# ApplicationShield.net
KiCad netlist of a schematic drawn in EAGLE
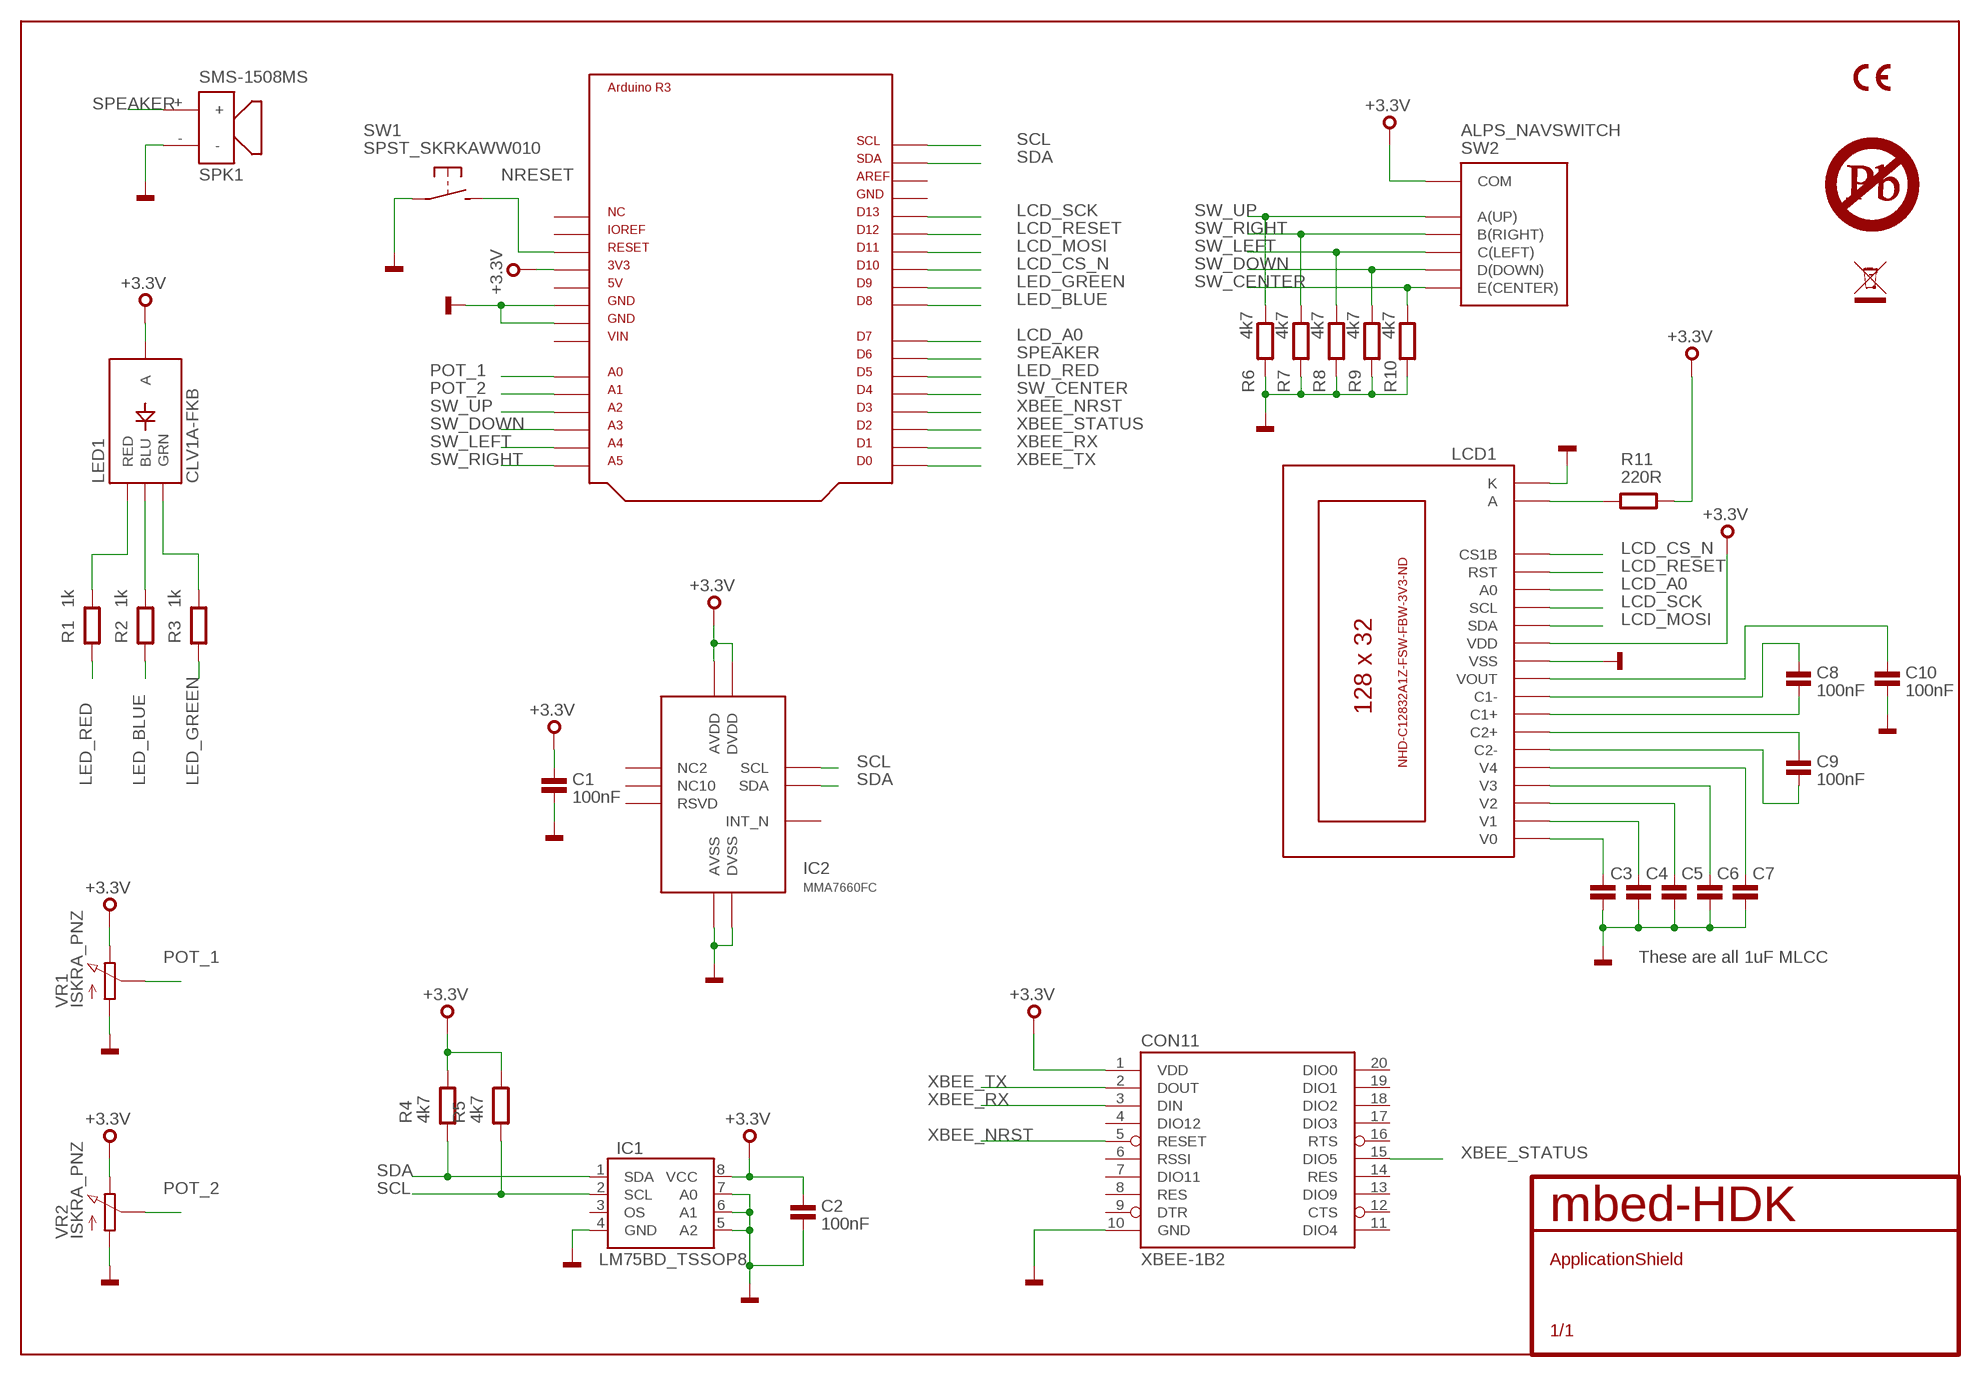
[diagram p0: schematic, sheet 1]

(export (version "E")
  (design (tool "Eeschema 10.0.6"))
  (components
    (comp (ref "BRD1")
      (value "ARDUINO_R3_APPS")
      (footprint "eagle-import:ARDUINO_R3_APPS_SHEILD")
      (libsource (lib "eagle-import") (part "ARDUINO_R3_APPS"))
    )
    (comp (ref "C1")
      (value "100nF")
      (footprint "eagle-import:0402")
      (libsource (lib "eagle-import") (part "C0402"))
    )
    (comp (ref "C2")
      (value "100nF")
      (footprint "eagle-import:0402")
      (libsource (lib "eagle-import") (part "C0402"))
    )
    (comp (ref "C3")
      (value "100nF")
      (footprint "eagle-import:0402")
      (libsource (lib "eagle-import") (part "C0402"))
    )
    (comp (ref "C4")
      (value "100nF")
      (footprint "eagle-import:0402")
      (libsource (lib "eagle-import") (part "C0402"))
    )
    (comp (ref "C5")
      (value "100nF")
      (footprint "eagle-import:0402")
      (libsource (lib "eagle-import") (part "C0402"))
    )
    (comp (ref "C6")
      (value "100nF")
      (footprint "eagle-import:0402")
      (libsource (lib "eagle-import") (part "C0402"))
    )
    (comp (ref "C7")
      (value "100nF")
      (footprint "eagle-import:0402")
      (libsource (lib "eagle-import") (part "C0402"))
    )
    (comp (ref "C8")
      (value "100nF")
      (footprint "eagle-import:0402")
      (libsource (lib "eagle-import") (part "C0402"))
    )
    (comp (ref "C9")
      (value "100nF")
      (footprint "eagle-import:0402")
      (libsource (lib "eagle-import") (part "C0402"))
    )
    (comp (ref "C10")
      (value "100nF")
      (footprint "eagle-import:0402")
      (libsource (lib "eagle-import") (part "C0402"))
    )
    (comp (ref "CON11")
      (value "XBEE-1B2")
      (footprint "eagle-import:XBEE-SILK")
      (libsource (lib "eagle-import") (part "XBEE-1B2"))
    )
    (comp (ref "IC1")
      (value "LM75BD_TSSOP8")
      (footprint "eagle-import:TSSOP8")
      (libsource (lib "eagle-import") (part "LM75BD_TSSOP8"))
    )
    (comp (ref "IC2")
      (value "MMA7660FC")
      (footprint "eagle-import:DFN10-3X3MM")
      (libsource (lib "eagle-import") (part "MMA7660FC"))
    )
    (comp (ref "LCD1")
      (value "C12832A1Z")
      (footprint "eagle-import:C12832A1Z")
      (libsource (lib "eagle-import") (part "C12832A1Z"))
    )
    (comp (ref "LED1")
      (value "CLV1A-FKB")
      (footprint "eagle-import:PLCC-4")
      (libsource (lib "eagle-import") (part "CLV1A-FKB"))
    )
    (comp (ref "R1")
      (value "1k")
      (footprint "eagle-import:0402")
      (libsource (lib "eagle-import") (part "R0402"))
    )
    (comp (ref "R2")
      (value "1k")
      (footprint "eagle-import:0402")
      (libsource (lib "eagle-import") (part "R0402"))
    )
    (comp (ref "R3")
      (value "1k")
      (footprint "eagle-import:0402")
      (libsource (lib "eagle-import") (part "R0402"))
    )
    (comp (ref "R4")
      (value "4k7")
      (footprint "eagle-import:0402")
      (libsource (lib "eagle-import") (part "R0402"))
    )
    (comp (ref "R5")
      (value "4k7")
      (footprint "eagle-import:0402")
      (libsource (lib "eagle-import") (part "R0402"))
    )
    (comp (ref "R6")
      (value "4k7")
      (footprint "eagle-import:0402")
      (libsource (lib "eagle-import") (part "R0402"))
    )
    (comp (ref "R7")
      (value "4k7")
      (footprint "eagle-import:0402")
      (libsource (lib "eagle-import") (part "R0402"))
    )
    (comp (ref "R8")
      (value "4k7")
      (footprint "eagle-import:0402")
      (libsource (lib "eagle-import") (part "R0402"))
    )
    (comp (ref "R9")
      (value "4k7")
      (footprint "eagle-import:0402")
      (libsource (lib "eagle-import") (part "R0402"))
    )
    (comp (ref "R10")
      (value "4k7")
      (footprint "eagle-import:0402")
      (libsource (lib "eagle-import") (part "R0402"))
    )
    (comp (ref "R11")
      (value "220R")
      (footprint "eagle-import:0402")
      (libsource (lib "eagle-import") (part "R0402"))
    )
    (comp (ref "SPK1")
      (value "SMS-1508MS")
      (footprint "eagle-import:SMS-1508MS-R")
      (libsource (lib "eagle-import") (part "SMS-1508MS"))
    )
    (comp (ref "SS1")
      (value "PB-MARK")
      (footprint "eagle-import:PB-MARK-0.2")
      (libsource (lib "eagle-import") (part "PB-MARK"))
    )
    (comp (ref "SS2")
      (value "CE-MARK")
      (footprint "eagle-import:CE-MARK-0.2")
      (libsource (lib "eagle-import") (part "CE-MARK"))
    )
    (comp (ref "SS3")
      (value "WEEE-MARK")
      (footprint "eagle-import:WEEE-MARK-0.2")
      (libsource (lib "eagle-import") (part "WEEE-MARK"))
    )
    (comp (ref "SW1")
      (value "SPST_SKRKAWW010")
      (footprint "eagle-import:SKRKAEE010")
      (libsource (lib "eagle-import") (part "SPST_SKRKAWW010"))
    )
    (comp (ref "SW2")
      (value "ALPS_NAVSWITCH")
      (footprint "eagle-import:SKRHA_SERIES")
      (libsource (lib "eagle-import") (part "ALPS_NAVSWITCH"))
    )
    (comp (ref "VR1")
      (value "ISKRA_PNZ")
      (footprint "eagle-import:CA14V")
      (libsource (lib "eagle-import") (part "ISKRA_PNZ"))
    )
    (comp (ref "VR2")
      (value "ISKRA_PNZ")
      (footprint "eagle-import:CA14V")
      (libsource (lib "eagle-import") (part "ISKRA_PNZ"))
    )
  )
  (nets
    (net (code "1") (name "+3.3V") (class "Default")
      (node (ref "BRD1") (pin "P$4") (pinfunction "P$4_P$4") (pintype "bidirectional"))
      (node (ref "C1") (pin "1") (pinfunction "P$1_1") (pintype "passive"))
      (node (ref "C2") (pin "1") (pinfunction "P$1_1") (pintype "passive"))
      (node (ref "CON11") (pin "1") (pinfunction "VDD_1") (pintype "passive"))
      (node (ref "IC1") (pin "8") (pinfunction "VCC_8") (pintype "bidirectional"))
      (node (ref "IC2") (pin "P$3") (pinfunction "AVDD_P$3") (pintype "bidirectional"))
      (node (ref "IC2") (pin "P$9") (pinfunction "DVDD_P$9") (pintype "bidirectional"))
      (node (ref "LCD1") (pin "P$12") (pinfunction "VDD_P$12") (pintype "bidirectional"))
      (node (ref "LED1") (pin "2") (pinfunction "A_2") (pintype "bidirectional"))
      (node (ref "R11") (pin "1") (pinfunction "P$1_1") (pintype "passive"))
      (node (ref "R4") (pin "2") (pinfunction "P$2_2") (pintype "passive"))
      (node (ref "R5") (pin "2") (pinfunction "P$2_2") (pintype "passive"))
      (node (ref "SW2") (pin "P$5") (pinfunction "COM_P$5") (pintype "bidirectional"))
      (node (ref "VR1") (pin "P$3") (pinfunction "E_P$3") (pintype "passive"))
      (node (ref "VR2") (pin "P$3") (pinfunction "E_P$3") (pintype "passive"))
    )
    (net (code "2") (name "/LCD_A0") (class "Default")
      (node (ref "BRD1") (pin "P$22") (pinfunction "P$22_P$22") (pintype "bidirectional"))
      (node (ref "LCD1") (pin "P$15") (pinfunction "A0_P$15") (pintype "bidirectional"))
    )
    (net (code "3") (name "/LCD_CS_N") (class "Default")
      (node (ref "BRD1") (pin "P$25") (pinfunction "P$25_P$25") (pintype "bidirectional"))
      (node (ref "LCD1") (pin "P$17") (pinfunction "CS1B_P$17") (pintype "bidirectional"))
    )
    (net (code "4") (name "/LCD_MOSI") (class "Default")
      (node (ref "BRD1") (pin "P$26") (pinfunction "P$26_P$26") (pintype "bidirectional"))
      (node (ref "LCD1") (pin "P$13") (pinfunction "SDA_P$13") (pintype "bidirectional"))
    )
    (net (code "5") (name "/LCD_RESET") (class "Default")
      (node (ref "BRD1") (pin "P$27") (pinfunction "P$27_P$27") (pintype "bidirectional"))
      (node (ref "LCD1") (pin "P$16") (pinfunction "RST_P$16") (pintype "bidirectional"))
    )
    (net (code "6") (name "/LCD_SCK") (class "Default")
      (node (ref "BRD1") (pin "P$28") (pinfunction "P$28_P$28") (pintype "bidirectional"))
      (node (ref "LCD1") (pin "P$14") (pinfunction "SCL_P$14") (pintype "bidirectional"))
    )
    (net (code "7") (name "/LED_BLUE") (class "Default")
      (node (ref "BRD1") (pin "P$23") (pinfunction "P$23_P$23") (pintype "bidirectional"))
      (node (ref "R2") (pin "1") (pinfunction "P$1_1") (pintype "passive"))
    )
    (net (code "8") (name "/LED_GREEN") (class "Default")
      (node (ref "BRD1") (pin "P$24") (pinfunction "P$24_P$24") (pintype "bidirectional"))
      (node (ref "R3") (pin "1") (pinfunction "P$1_1") (pintype "passive"))
    )
    (net (code "9") (name "/LED_RED") (class "Default")
      (node (ref "BRD1") (pin "P$20") (pinfunction "P$20_P$20") (pintype "bidirectional"))
      (node (ref "R1") (pin "1") (pinfunction "P$1_1") (pintype "passive"))
    )
    (net (code "10") (name "/NRESET") (class "Default")
      (node (ref "BRD1") (pin "P$3") (pinfunction "P$3_P$3") (pintype "bidirectional"))
      (node (ref "SW1") (pin "P$2") (pinfunction "S_P$2") (pintype "passive"))
    )
    (net (code "11") (name "/POT_1") (class "Default")
      (node (ref "BRD1") (pin "P$9") (pinfunction "P$9_P$9") (pintype "bidirectional"))
      (node (ref "VR1") (pin "P$2") (pinfunction "S_P$2") (pintype "passive"))
    )
    (net (code "12") (name "/POT_2") (class "Default")
      (node (ref "BRD1") (pin "P$10") (pinfunction "P$10_P$10") (pintype "bidirectional"))
      (node (ref "VR2") (pin "P$2") (pinfunction "S_P$2") (pintype "passive"))
    )
    (net (code "13") (name "/SCL") (class "Default")
      (node (ref "BRD1") (pin "P$32") (pinfunction "P$32_P$32") (pintype "bidirectional"))
      (node (ref "IC1") (pin "2") (pinfunction "SCL_2") (pintype "bidirectional"))
      (node (ref "IC2") (pin "P$6") (pinfunction "SCL_P$6") (pintype "bidirectional"))
      (node (ref "R5") (pin "1") (pinfunction "P$1_1") (pintype "passive"))
    )
    (net (code "14") (name "/SDA") (class "Default")
      (node (ref "BRD1") (pin "P$31") (pinfunction "P$31_P$31") (pintype "bidirectional"))
      (node (ref "IC1") (pin "1") (pinfunction "SDA_1") (pintype "bidirectional"))
      (node (ref "IC2") (pin "P$7") (pinfunction "SDA_P$7") (pintype "bidirectional"))
      (node (ref "R4") (pin "1") (pinfunction "P$1_1") (pintype "passive"))
    )
    (net (code "15") (name "/SPEAKER") (class "Default")
      (node (ref "BRD1") (pin "P$21") (pinfunction "P$21_P$21") (pintype "bidirectional"))
      (node (ref "SPK1") (pin "+") (pinfunction "+_+") (pintype "bidirectional"))
    )
    (net (code "16") (name "/SW_CENTER") (class "Default")
      (node (ref "BRD1") (pin "P$19") (pinfunction "P$19_P$19") (pintype "bidirectional"))
      (node (ref "R10") (pin "1") (pinfunction "P$1_1") (pintype "passive"))
      (node (ref "SW2") (pin "P$2") (pinfunction "E(CENTER)_P$2") (pintype "bidirectional"))
    )
    (net (code "17") (name "/SW_DOWN") (class "Default")
      (node (ref "BRD1") (pin "P$12") (pinfunction "P$12_P$12") (pintype "bidirectional"))
      (node (ref "R9") (pin "1") (pinfunction "P$1_1") (pintype "passive"))
      (node (ref "SW2") (pin "P$4") (pinfunction "D(DOWN)_P$4") (pintype "bidirectional"))
    )
    (net (code "18") (name "/SW_LEFT") (class "Default")
      (node (ref "BRD1") (pin "P$13") (pinfunction "P$13_P$13") (pintype "bidirectional"))
      (node (ref "R8") (pin "1") (pinfunction "P$1_1") (pintype "passive"))
      (node (ref "SW2") (pin "P$1") (pinfunction "C(LEFT)_P$1") (pintype "bidirectional"))
    )
    (net (code "19") (name "/SW_RIGHT") (class "Default")
      (node (ref "BRD1") (pin "P$14") (pinfunction "P$14_P$14") (pintype "bidirectional"))
      (node (ref "R7") (pin "1") (pinfunction "P$1_1") (pintype "passive"))
      (node (ref "SW2") (pin "P$6") (pinfunction "B(RIGHT)_P$6") (pintype "bidirectional"))
    )
    (net (code "20") (name "/SW_UP") (class "Default")
      (node (ref "BRD1") (pin "P$11") (pinfunction "P$11_P$11") (pintype "bidirectional"))
      (node (ref "R6") (pin "1") (pinfunction "P$1_1") (pintype "passive"))
      (node (ref "SW2") (pin "P$3") (pinfunction "A(UP)_P$3") (pintype "bidirectional"))
    )
    (net (code "21") (name "/XBEE_NRST") (class "Default")
      (node (ref "BRD1") (pin "P$18") (pinfunction "P$18_P$18") (pintype "bidirectional"))
      (node (ref "CON11") (pin "5") (pinfunction "RESET_5") (pintype "input"))
    )
    (net (code "22") (name "/XBEE_RX") (class "Default")
      (node (ref "BRD1") (pin "P$16") (pinfunction "P$16_P$16") (pintype "bidirectional"))
      (node (ref "CON11") (pin "3") (pinfunction "DIN_3") (pintype "input"))
    )
    (net (code "23") (name "/XBEE_STATUS") (class "Default")
      (node (ref "BRD1") (pin "P$17") (pinfunction "P$17_P$17") (pintype "bidirectional"))
      (node (ref "CON11") (pin "15") (pinfunction "DIO5_15") (pintype "bidirectional"))
    )
    (net (code "24") (name "/XBEE_TX") (class "Default")
      (node (ref "BRD1") (pin "P$15") (pinfunction "P$15_P$15") (pintype "bidirectional"))
      (node (ref "CON11") (pin "2") (pinfunction "DOUT_2") (pintype "output"))
    )
    (net (code "25") (name "GND") (class "Default")
      (node (ref "BRD1") (pin "P$6") (pinfunction "P$6_P$6") (pintype "bidirectional"))
      (node (ref "BRD1") (pin "P$7") (pinfunction "P$7_P$7") (pintype "bidirectional"))
      (node (ref "C1") (pin "2") (pinfunction "P$2_2") (pintype "passive"))
      (node (ref "C10") (pin "2") (pinfunction "P$2_2") (pintype "passive"))
      (node (ref "C2") (pin "2") (pinfunction "P$2_2") (pintype "passive"))
      (node (ref "C3") (pin "2") (pinfunction "P$2_2") (pintype "passive"))
      (node (ref "C4") (pin "2") (pinfunction "P$2_2") (pintype "passive"))
      (node (ref "C5") (pin "2") (pinfunction "P$2_2") (pintype "passive"))
      (node (ref "C6") (pin "2") (pinfunction "P$2_2") (pintype "passive"))
      (node (ref "C7") (pin "2") (pinfunction "P$2_2") (pintype "passive"))
      (node (ref "CON11") (pin "10") (pinfunction "GND_10") (pintype "power_in"))
      (node (ref "IC1") (pin "4") (pinfunction "GND_4") (pintype "bidirectional"))
      (node (ref "IC1") (pin "5") (pinfunction "A2_5") (pintype "bidirectional"))
      (node (ref "IC1") (pin "6") (pinfunction "A1_6") (pintype "bidirectional"))
      (node (ref "IC1") (pin "7") (pinfunction "A0_7") (pintype "bidirectional"))
      (node (ref "IC2") (pin "P$4") (pinfunction "AVSS_P$4") (pintype "bidirectional"))
      (node (ref "IC2") (pin "P$8") (pinfunction "DVSS_P$8") (pintype "bidirectional"))
      (node (ref "LCD1") (pin "K") (pinfunction "K_K") (pintype "bidirectional"))
      (node (ref "LCD1") (pin "P$11") (pinfunction "VSS_P$11") (pintype "bidirectional"))
      (node (ref "R10") (pin "2") (pinfunction "P$2_2") (pintype "passive"))
      (node (ref "R6") (pin "2") (pinfunction "P$2_2") (pintype "passive"))
      (node (ref "R7") (pin "2") (pinfunction "P$2_2") (pintype "passive"))
      (node (ref "R8") (pin "2") (pinfunction "P$2_2") (pintype "passive"))
      (node (ref "R9") (pin "2") (pinfunction "P$2_2") (pintype "passive"))
      (node (ref "SPK1") (pin "-") (pinfunction "-_-") (pintype "bidirectional"))
      (node (ref "SW1") (pin "P$1") (pinfunction "P_P$1") (pintype "passive"))
      (node (ref "VR1") (pin "P$1") (pinfunction "A_P$1") (pintype "passive"))
      (node (ref "VR2") (pin "P$1") (pinfunction "A_P$1") (pintype "passive"))
    )
    (net (code "26") (name "Net-(C3-P$1)") (class "Default")
      (node (ref "C3") (pin "1") (pinfunction "P$1_1") (pintype "passive"))
      (node (ref "LCD1") (pin "P$1") (pinfunction "V0_P$1") (pintype "bidirectional"))
    )
    (net (code "27") (name "Net-(C4-P$1)") (class "Default")
      (node (ref "C4") (pin "1") (pinfunction "P$1_1") (pintype "passive"))
      (node (ref "LCD1") (pin "P$2") (pinfunction "V1_P$2") (pintype "bidirectional"))
    )
    (net (code "28") (name "Net-(C5-P$1)") (class "Default")
      (node (ref "C5") (pin "1") (pinfunction "P$1_1") (pintype "passive"))
      (node (ref "LCD1") (pin "P$3") (pinfunction "V2_P$3") (pintype "bidirectional"))
    )
    (net (code "29") (name "Net-(C6-P$1)") (class "Default")
      (node (ref "C6") (pin "1") (pinfunction "P$1_1") (pintype "passive"))
      (node (ref "LCD1") (pin "P$4") (pinfunction "V3_P$4") (pintype "bidirectional"))
    )
    (net (code "30") (name "Net-(C7-P$1)") (class "Default")
      (node (ref "C7") (pin "1") (pinfunction "P$1_1") (pintype "passive"))
      (node (ref "LCD1") (pin "P$5") (pinfunction "V4_P$5") (pintype "bidirectional"))
    )
    (net (code "31") (name "Net-(C8-P$1)") (class "Default")
      (node (ref "C8") (pin "1") (pinfunction "P$1_1") (pintype "passive"))
      (node (ref "LCD1") (pin "P$9") (pinfunction "C1-_P$9") (pintype "bidirectional"))
    )
    (net (code "32") (name "Net-(C8-P$2)") (class "Default")
      (node (ref "C8") (pin "2") (pinfunction "P$2_2") (pintype "passive"))
      (node (ref "LCD1") (pin "P$8") (pinfunction "C1+_P$8") (pintype "bidirectional"))
    )
    (net (code "33") (name "Net-(C9-P$1)") (class "Default")
      (node (ref "C9") (pin "1") (pinfunction "P$1_1") (pintype "passive"))
      (node (ref "LCD1") (pin "P$7") (pinfunction "C2+_P$7") (pintype "bidirectional"))
    )
    (net (code "34") (name "Net-(C9-P$2)") (class "Default")
      (node (ref "C9") (pin "2") (pinfunction "P$2_2") (pintype "passive"))
      (node (ref "LCD1") (pin "P$6") (pinfunction "C2-_P$6") (pintype "bidirectional"))
    )
    (net (code "35") (name "Net-(C10-P$1)") (class "Default")
      (node (ref "C10") (pin "1") (pinfunction "P$1_1") (pintype "passive"))
      (node (ref "LCD1") (pin "P$10") (pinfunction "VOUT_P$10") (pintype "bidirectional"))
    )
    (net (code "36") (name "Net-(LED1-BLU)") (class "Default")
      (node (ref "LED1") (pin "3") (pinfunction "BLU_3") (pintype "bidirectional"))
      (node (ref "R2") (pin "2") (pinfunction "P$2_2") (pintype "passive"))
    )
    (net (code "37") (name "Net-(LED1-GRN)") (class "Default")
      (node (ref "LED1") (pin "4") (pinfunction "GRN_4") (pintype "bidirectional"))
      (node (ref "R3") (pin "2") (pinfunction "P$2_2") (pintype "passive"))
    )
    (net (code "38") (name "Net-(LED1-RED)") (class "Default")
      (node (ref "LED1") (pin "1") (pinfunction "RED_1") (pintype "bidirectional"))
      (node (ref "R1") (pin "2") (pinfunction "P$2_2") (pintype "passive"))
    )
    (net (code "39") (name "Net-(R11-P$2)") (class "Default")
      (node (ref "LCD1") (pin "A") (pinfunction "A_A") (pintype "bidirectional"))
      (node (ref "R11") (pin "2") (pinfunction "P$2_2") (pintype "passive"))
    )
    (net (code "40") (name "unconnected-(BRD1-PadP$1)") (class "Default")
      (node (ref "BRD1") (pin "P$1") (pinfunction "P$1_P$1") (pintype "bidirectional"))
    )
    (net (code "41") (name "unconnected-(BRD1-PadP$2)") (class "Default")
      (node (ref "BRD1") (pin "P$2") (pinfunction "P$2_P$2") (pintype "bidirectional"))
    )
    (net (code "42") (name "unconnected-(BRD1-PadP$5)") (class "Default")
      (node (ref "BRD1") (pin "P$5") (pinfunction "P$5_P$5") (pintype "bidirectional"))
    )
    (net (code "43") (name "unconnected-(BRD1-PadP$8)") (class "Default")
      (node (ref "BRD1") (pin "P$8") (pinfunction "P$8_P$8") (pintype "bidirectional"))
    )
    (net (code "44") (name "unconnected-(BRD1-PadP$29)") (class "Default")
      (node (ref "BRD1") (pin "P$29") (pinfunction "P$29_P$29") (pintype "bidirectional"))
    )
    (net (code "45") (name "unconnected-(BRD1-PadP$30)") (class "Default")
      (node (ref "BRD1") (pin "P$30") (pinfunction "P$30_P$30") (pintype "bidirectional"))
    )
    (net (code "46") (name "unconnected-(CON11-CTS-Pad12)") (class "Default")
      (node (ref "CON11") (pin "12") (pinfunction "CTS_12") (pintype "output"))
    )
    (net (code "47") (name "unconnected-(CON11-DIO0-Pad20)") (class "Default")
      (node (ref "CON11") (pin "20") (pinfunction "DIO0_20") (pintype "bidirectional"))
    )
    (net (code "48") (name "unconnected-(CON11-DIO1-Pad19)") (class "Default")
      (node (ref "CON11") (pin "19") (pinfunction "DIO1_19") (pintype "bidirectional"))
    )
    (net (code "49") (name "unconnected-(CON11-DIO2-Pad18)") (class "Default")
      (node (ref "CON11") (pin "18") (pinfunction "DIO2_18") (pintype "bidirectional"))
    )
    (net (code "50") (name "unconnected-(CON11-DIO3-Pad17)") (class "Default")
      (node (ref "CON11") (pin "17") (pinfunction "DIO3_17") (pintype "bidirectional"))
    )
    (net (code "51") (name "unconnected-(CON11-DIO4-Pad11)") (class "Default")
      (node (ref "CON11") (pin "11") (pinfunction "DIO4_11") (pintype "bidirectional"))
    )
    (net (code "52") (name "unconnected-(CON11-DIO9-Pad13)") (class "Default")
      (node (ref "CON11") (pin "13") (pinfunction "DIO9_13") (pintype "bidirectional"))
    )
    (net (code "53") (name "unconnected-(CON11-DIO11-Pad7)") (class "Default")
      (node (ref "CON11") (pin "7") (pinfunction "DIO11_7") (pintype "bidirectional"))
    )
    (net (code "54") (name "unconnected-(CON11-DIO12-Pad4)") (class "Default")
      (node (ref "CON11") (pin "4") (pinfunction "DIO12_4") (pintype "bidirectional"))
    )
    (net (code "55") (name "unconnected-(CON11-DTR-Pad9)") (class "Default")
      (node (ref "CON11") (pin "9") (pinfunction "DTR_9") (pintype "bidirectional"))
    )
    (net (code "56") (name "unconnected-(CON11-RES-Pad8)") (class "Default")
      (node (ref "CON11") (pin "8") (pinfunction "RES_8") (pintype "bidirectional"))
    )
    (net (code "57") (name "unconnected-(CON11-RES-Pad14)") (class "Default")
      (node (ref "CON11") (pin "14") (pinfunction "RES_14") (pintype "bidirectional"))
    )
    (net (code "58") (name "unconnected-(CON11-RSSI-Pad6)") (class "Default")
      (node (ref "CON11") (pin "6") (pinfunction "RSSI_6") (pintype "bidirectional"))
    )
    (net (code "59") (name "unconnected-(CON11-RTS-Pad16)") (class "Default")
      (node (ref "CON11") (pin "16") (pinfunction "RTS_16") (pintype "passive"))
    )
    (net (code "60") (name "unconnected-(IC1-OS-Pad3)") (class "Default")
      (node (ref "IC1") (pin "3") (pinfunction "OS_3") (pintype "bidirectional"))
    )
    (net (code "61") (name "unconnected-(IC2-INT_N-PadP$5)") (class "Default")
      (node (ref "IC2") (pin "P$5") (pinfunction "INT_N_P$5") (pintype "bidirectional"))
    )
    (net (code "62") (name "unconnected-(IC2-NC2-PadP$2)") (class "Default")
      (node (ref "IC2") (pin "P$2") (pinfunction "NC2_P$2") (pintype "bidirectional"))
    )
    (net (code "63") (name "unconnected-(IC2-NC10-PadP$10)") (class "Default")
      (node (ref "IC2") (pin "P$10") (pinfunction "NC10_P$10") (pintype "bidirectional"))
    )
    (net (code "64") (name "unconnected-(IC2-RSVD-PadP$1)") (class "Default")
      (node (ref "IC2") (pin "P$1") (pinfunction "RSVD_P$1") (pintype "bidirectional"))
    )
  )
)
